# Sheet_MachMQ3.net
KiCad netlist of a schematic drawn in Altium Designer
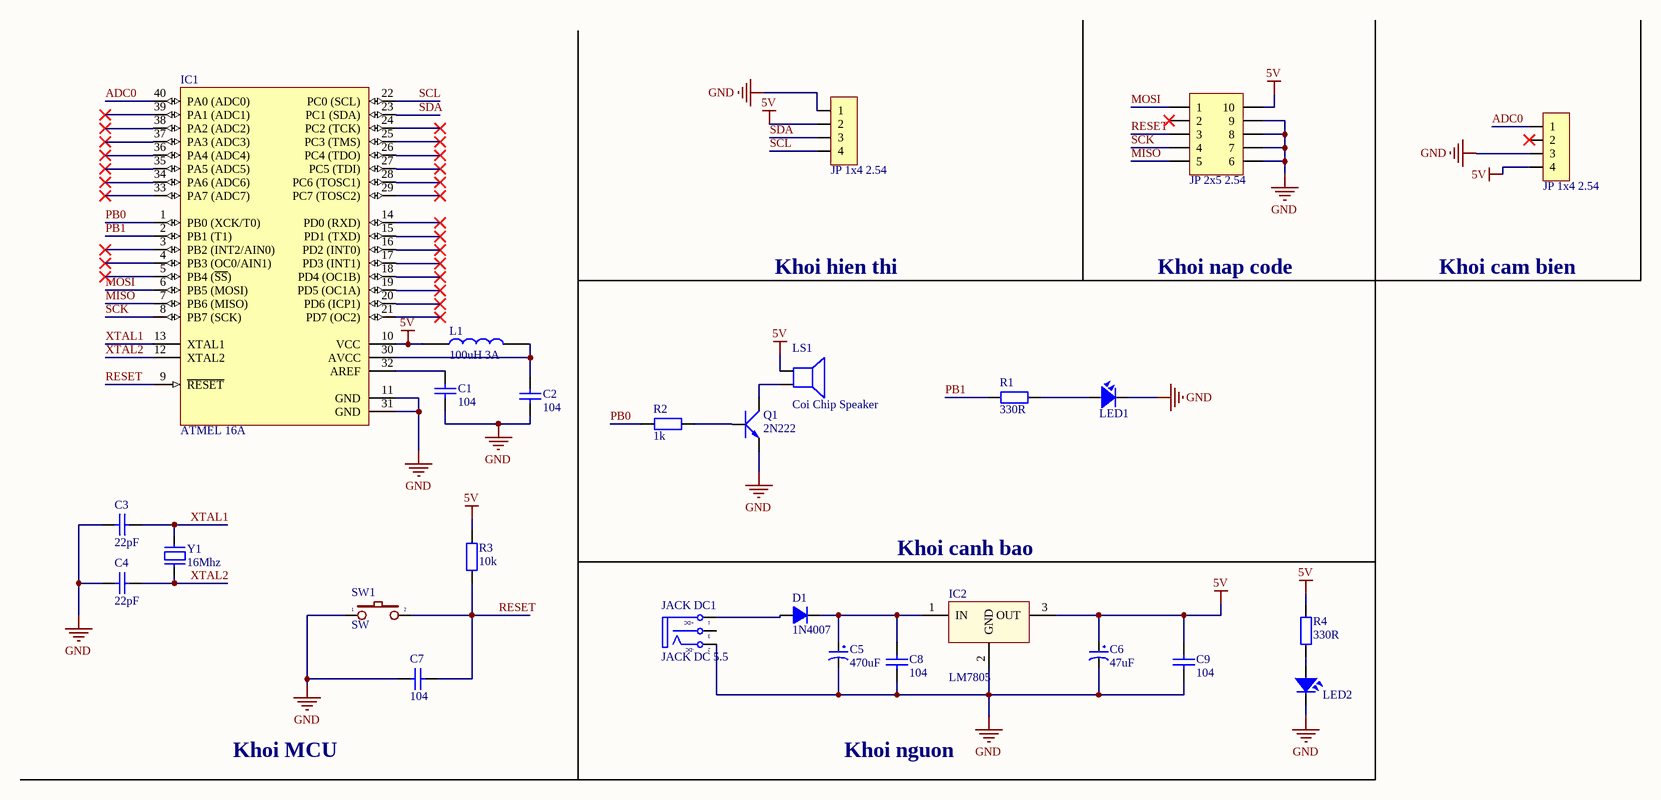
[diagram p0: Sheet_MachMQ3.SchDoc]

(export (version "E")
  (design (tool "Eeschema 10.0.6"))
  (components
    (comp (ref "C1")
      (value "104")
      (footprint "tu gom")
      (description "Cắm")
      (libsource (lib "Capacitor") (part "Tu gom 104 50V"))
    )
    (comp (ref "C2")
      (value "104")
      (footprint "tu gom")
      (description "Cắm")
      (libsource (lib "Capacitor") (part "Tu gom 104 50V"))
    )
    (comp (ref "C3")
      (value "22pF")
      (footprint "tu gom")
      (description "Cắm")
      (libsource (lib "Capacitor") (part "Tu gom 22pF 50V"))
    )
    (comp (ref "C4")
      (value "22pF")
      (footprint "tu gom")
      (description "Cắm")
      (libsource (lib "Capacitor") (part "Tu gom 22pF 50V"))
    )
    (comp (ref "C5")
      (value "470uF")
      (footprint "tu hoa 8mm")
      (description "Cắm")
      (libsource (lib "Capacitor") (part "Tu Hoa 470uF 16V 8x11"))
    )
    (comp (ref "C6")
      (value "47uF")
      (footprint "tu hoa 5mm")
      (description "Cắm")
      (libsource (lib "Capacitor") (part "Tu Hoa 47uF 16V 5x10"))
    )
    (comp (ref "C7")
      (value "104")
      (footprint "tu gom")
      (description "Cắm")
      (libsource (lib "Capacitor") (part "Tu gom 104 50V"))
    )
    (comp (ref "C8")
      (value "104")
      (footprint "tu gom")
      (description "Cắm")
      (libsource (lib "Capacitor") (part "Tu gom 104 50V"))
    )
    (comp (ref "C9")
      (value "104")
      (footprint "tu gom")
      (description "Cắm")
      (libsource (lib "Capacitor") (part "Tu gom 104 50V"))
    )
    (comp (ref "D1")
      (value "1N4007")
      (footprint "D1A")
      (description "Diode 1A")
      (libsource (lib "My Library") (part "D1A"))
    )
    (comp (ref "IC1")
      (value "ATMEL 16A")
      (footprint "DIP40/W0.6")
      (description "8-Bit AVR Microcontroller with 16K Bytes of In-System Programmable Flash Memory")
      (libsource (lib "My Library") (part "ATmega16A-PU"))
    )
    (comp (ref "IC2")
      (value "LM7805")
      (footprint "QTO-220H3")
      (description "On ap +, from + 5 to + 24VDC")
      (libsource (lib "My Library") (part "LM78xx"))
    )
    (comp (ref "JACK DC1")
      (value "JACK DC 5.5")
      (footprint "JACK DC 5.5")
      (libsource (lib "Component") (part "JACK DC 5.5"))
    )
    (comp (ref "JP1")
      (value "JP 1x4 2.54")
      (footprint "JP 1x4 CT")
      (description "Cắm")
      (libsource (lib "Jump") (part "JP 1x4 2.54 Cai Thang"))
    )
    (comp (ref "JP2")
      (value "JP 2x5 2.54")
      (footprint "JP 2x5 DT")
      (description "Cắm")
      (libsource (lib "Jump") (part "JP 2x5 2.54 Duc Thang"))
    )
    (comp (ref "JP3")
      (value "JP 1x4 2.54")
      (footprint "JP 1x4 CT")
      (description "Cắm")
      (libsource (lib "Jump") (part "JP 1x4 2.54 Cai Thang"))
    )
    (comp (ref "L1")
      (value "100uH 3A")
      (footprint "CUON CAM 100uH3A")
      (description "Dán")
      (libsource (lib "Inductor") (part "CUON CAM 100uH DIP"))
    )
    (comp (ref "LED1")
      (value "LED")
      (footprint "LED-3MM-RED")
      (description "LED Single colour Green and Red")
      (libsource (lib "LIBRARY") (part "LED"))
    )
    (comp (ref "LED2")
      (value "LED")
      (footprint "LED-3MM-RED")
      (description "LED Single colour Green and Red")
      (libsource (lib "LIBRARY") (part "LED"))
    )
    (comp (ref "LS1")
      (value "Coi Chip Speaker")
      (footprint "Coi Chip Speacker")
      (description "Còi chip")
      (libsource (lib "Component") (part "Coi Chip Speaker"))
    )
    (comp (ref "Q1")
      (value "2N222")
      (footprint "TO92-123")
      (description "NPN 600mW, ECB")
      (libsource (lib "LIBRARY") (part "2N222"))
    )
    (comp (ref "R1")
      (value "330R")
      (footprint "tro vach 1/2w")
      (description "Cắm")
      (libsource (lib "Resistor") (part "Tro Vach 1/2W 5% 330R"))
    )
    (comp (ref "R2")
      (value "1k")
      (footprint "tro vach 1/2w")
      (description "Cắm")
      (libsource (lib "Resistor") (part "Tro Vach 1/2W 5% 1k"))
    )
    (comp (ref "R3")
      (value "10k")
      (footprint "tro vach 1/2w")
      (description "Cắm")
      (libsource (lib "Resistor") (part "Tro Vach 1/2W 5% 10k"))
    )
    (comp (ref "R4")
      (value "330R")
      (footprint "tro vach 1/2w")
      (description "Cắm")
      (libsource (lib "Resistor") (part "Tro Vach 1/2W 5% 330R"))
    )
    (comp (ref "SW1")
      (value "SW")
      (footprint "SW2")
      (description "Switch button 2 pin")
      (libsource (lib "Library AL") (part "SW2"))
    )
    (comp (ref "Y1")
      (value "16Mhz")
      (footprint "Thach Anh 2 chan cam")
      (description "Crystal For all Crystal 2pin.")
      (libsource (lib "Component") (part "Thach Anh 2 chan Cam"))
    )
  )
  (nets
    (net (code "1") (name "/ADC0") (class "Default")
      (node (ref "IC1") (pin "40") (pinfunction "PA0_(ADC0)_40") (pintype "bidirectional"))
      (node (ref "JP1") (pin "1") (pinfunction "1_1") (pintype "passive"))
    )
    (net (code "2") (name "/MISO") (class "Default")
      (node (ref "IC1") (pin "7") (pinfunction "PB6_(MISO)_7") (pintype "bidirectional"))
      (node (ref "JP2") (pin "5") (pinfunction "5_5") (pintype "passive"))
    )
    (net (code "3") (name "/MOSI") (class "Default")
      (node (ref "IC1") (pin "6") (pinfunction "PB5_(MOSI)_6") (pintype "bidirectional"))
      (node (ref "JP2") (pin "1") (pinfunction "1_1") (pintype "passive"))
    )
    (net (code "4") (name "/PB0") (class "Default")
      (node (ref "IC1") (pin "1") (pinfunction "PB0_(XCK/T0)_1") (pintype "bidirectional"))
      (node (ref "R2") (pin "1") (pinfunction "1_1") (pintype "passive"))
    )
    (net (code "5") (name "/PB1") (class "Default")
      (node (ref "IC1") (pin "2") (pinfunction "PB1_(T1)_2") (pintype "bidirectional"))
      (node (ref "R1") (pin "1") (pinfunction "1_1") (pintype "passive"))
    )
    (net (code "6") (name "/RESET") (class "Default")
      (node (ref "C7") (pin "1") (pinfunction "1_1") (pintype "passive"))
      (node (ref "IC1") (pin "9") (pinfunction "~{RESET}_9") (pintype "input"))
      (node (ref "JP2") (pin "3") (pinfunction "3_3") (pintype "passive"))
      (node (ref "R3") (pin "1") (pinfunction "1_1") (pintype "passive"))
      (node (ref "SW1") (pin "2") (pinfunction "2_2") (pintype "passive"))
    )
    (net (code "7") (name "/SCK") (class "Default")
      (node (ref "IC1") (pin "8") (pinfunction "PB7_(SCK)_8") (pintype "bidirectional"))
      (node (ref "JP2") (pin "4") (pinfunction "4_4") (pintype "passive"))
    )
    (net (code "8") (name "/SCL") (class "Default")
      (node (ref "IC1") (pin "22") (pinfunction "PC0_(SCL)_22") (pintype "bidirectional"))
      (node (ref "JP3") (pin "4") (pinfunction "4_4") (pintype "passive"))
    )
    (net (code "9") (name "/SDA") (class "Default")
      (node (ref "IC1") (pin "23") (pinfunction "PC1_(SDA)_23") (pintype "bidirectional"))
      (node (ref "JP3") (pin "3") (pinfunction "3_3") (pintype "passive"))
    )
    (net (code "10") (name "/XTAL1") (class "Default")
      (node (ref "C3") (pin "1") (pinfunction "1_1") (pintype "passive"))
      (node (ref "IC1") (pin "13") (pinfunction "XTAL1_13") (pintype "passive"))
      (node (ref "Y1") (pin "2") (pinfunction "2_2") (pintype "passive"))
    )
    (net (code "11") (name "/XTAL2") (class "Default")
      (node (ref "C4") (pin "1") (pinfunction "1_1") (pintype "passive"))
      (node (ref "IC1") (pin "12") (pinfunction "XTAL2_12") (pintype "passive"))
      (node (ref "Y1") (pin "1") (pinfunction "1_1") (pintype "passive"))
    )
    (net (code "12") (name "5V") (class "Default")
      (node (ref "C6") (pin "1") (pinfunction "1_1") (pintype "passive"))
      (node (ref "C9") (pin "1") (pinfunction "1_1") (pintype "passive"))
      (node (ref "IC1") (pin "10") (pinfunction "VCC_10") (pintype "power_in"))
      (node (ref "IC2") (pin "3") (pinfunction "OUT_3") (pintype "passive"))
      (node (ref "JP1") (pin "4") (pinfunction "4_4") (pintype "passive"))
      (node (ref "JP2") (pin "10") (pinfunction "10_10") (pintype "passive"))
      (node (ref "JP3") (pin "2") (pinfunction "2_2") (pintype "passive"))
      (node (ref "L1") (pin "1") (pinfunction "1_1") (pintype "passive"))
      (node (ref "LS1") (pin "1") (pinfunction "1_1") (pintype "passive"))
      (node (ref "R3") (pin "2") (pinfunction "2_2") (pintype "passive"))
      (node (ref "R4") (pin "2") (pinfunction "2_2") (pintype "passive"))
    )
    (net (code "13") (name "GND") (class "Default")
      (node (ref "C1") (pin "2") (pinfunction "2_2") (pintype "passive"))
      (node (ref "C2") (pin "2") (pinfunction "2_2") (pintype "passive"))
      (node (ref "C3") (pin "2") (pinfunction "2_2") (pintype "passive"))
      (node (ref "C4") (pin "2") (pinfunction "2_2") (pintype "passive"))
      (node (ref "C5") (pin "2") (pinfunction "2_2") (pintype "passive"))
      (node (ref "C6") (pin "2") (pinfunction "2_2") (pintype "passive"))
      (node (ref "C7") (pin "2") (pinfunction "2_2") (pintype "passive"))
      (node (ref "C8") (pin "2") (pinfunction "2_2") (pintype "passive"))
      (node (ref "C9") (pin "2") (pinfunction "2_2") (pintype "passive"))
      (node (ref "IC1") (pin "11") (pinfunction "GND_11") (pintype "power_in"))
      (node (ref "IC1") (pin "31") (pinfunction "GND_31") (pintype "power_in"))
      (node (ref "IC2") (pin "2") (pinfunction "GND_2") (pintype "passive"))
      (node (ref "JACK DC1") (pin "2") (pinfunction "TN_2") (pintype "passive"))
      (node (ref "JP1") (pin "3") (pinfunction "3_3") (pintype "passive"))
      (node (ref "JP2") (pin "6") (pinfunction "6_6") (pintype "passive"))
      (node (ref "JP2") (pin "7") (pinfunction "7_7") (pintype "passive"))
      (node (ref "JP2") (pin "8") (pinfunction "8_8") (pintype "passive"))
      (node (ref "JP2") (pin "9") (pinfunction "9_9") (pintype "passive"))
      (node (ref "JP3") (pin "1") (pinfunction "1_1") (pintype "passive"))
      (node (ref "LED1") (pin "2") (pinfunction "2_2") (pintype "passive"))
      (node (ref "LED2") (pin "2") (pinfunction "2_2") (pintype "passive"))
      (node (ref "Q1") (pin "1") (pinfunction "E_1") (pintype "passive"))
      (node (ref "SW1") (pin "1") (pinfunction "1_1") (pintype "passive"))
    )
    (net (code "14") (name "Net-(D1-A)") (class "Default")
      (node (ref "D1") (pin "1") (pinfunction "A_1") (pintype "passive"))
      (node (ref "JACK DC1") (pin "1") (pinfunction "T_1") (pintype "passive"))
    )
    (net (code "15") (name "Net-(D1-K)") (class "Default")
      (node (ref "C5") (pin "1") (pinfunction "1_1") (pintype "passive"))
      (node (ref "C8") (pin "1") (pinfunction "1_1") (pintype "passive"))
      (node (ref "D1") (pin "2") (pinfunction "K_2") (pintype "passive"))
      (node (ref "IC2") (pin "1") (pinfunction "IN_1") (pintype "passive"))
    )
    (net (code "16") (name "Net-(IC1-AREF)") (class "Default")
      (node (ref "C1") (pin "1") (pinfunction "1_1") (pintype "passive"))
      (node (ref "IC1") (pin "32") (pinfunction "AREF_32") (pintype "power_in"))
    )
    (net (code "17") (name "Net-(IC1-AVCC)") (class "Default")
      (node (ref "C2") (pin "1") (pinfunction "1_1") (pintype "passive"))
      (node (ref "IC1") (pin "30") (pinfunction "AVCC_30") (pintype "power_in"))
      (node (ref "L1") (pin "2") (pinfunction "2_2") (pintype "passive"))
    )
    (net (code "18") (name "Net-(LED1-Pad1)") (class "Default")
      (node (ref "LED1") (pin "1") (pinfunction "1_1") (pintype "passive"))
      (node (ref "R1") (pin "2") (pinfunction "2_2") (pintype "passive"))
    )
    (net (code "19") (name "Net-(LED2-Pad1)") (class "Default")
      (node (ref "LED2") (pin "1") (pinfunction "1_1") (pintype "passive"))
      (node (ref "R4") (pin "1") (pinfunction "1_1") (pintype "passive"))
    )
    (net (code "20") (name "Net-(Q1-B)") (class "Default")
      (node (ref "Q1") (pin "2") (pinfunction "B_2") (pintype "passive"))
      (node (ref "R2") (pin "2") (pinfunction "2_2") (pintype "passive"))
    )
    (net (code "21") (name "Net-(Q1-C)") (class "Default")
      (node (ref "LS1") (pin "2") (pinfunction "2_2") (pintype "passive"))
      (node (ref "Q1") (pin "3") (pinfunction "C_3") (pintype "passive"))
    )
    (net (code "22") (name "unconnected-(IC1-PA1_(ADC1)-Pad39)") (class "Default")
      (node (ref "IC1") (pin "39") (pinfunction "PA1_(ADC1)_39") (pintype "bidirectional+no_connect"))
    )
    (net (code "23") (name "unconnected-(IC1-PA2_(ADC2)-Pad38)") (class "Default")
      (node (ref "IC1") (pin "38") (pinfunction "PA2_(ADC2)_38") (pintype "bidirectional+no_connect"))
    )
    (net (code "24") (name "unconnected-(IC1-PA3_(ADC3)-Pad37)") (class "Default")
      (node (ref "IC1") (pin "37") (pinfunction "PA3_(ADC3)_37") (pintype "bidirectional+no_connect"))
    )
    (net (code "25") (name "unconnected-(IC1-PA4_(ADC4)-Pad36)") (class "Default")
      (node (ref "IC1") (pin "36") (pinfunction "PA4_(ADC4)_36") (pintype "bidirectional+no_connect"))
    )
    (net (code "26") (name "unconnected-(IC1-PA5_(ADC5)-Pad35)") (class "Default")
      (node (ref "IC1") (pin "35") (pinfunction "PA5_(ADC5)_35") (pintype "bidirectional+no_connect"))
    )
    (net (code "27") (name "unconnected-(IC1-PA6_(ADC6)-Pad34)") (class "Default")
      (node (ref "IC1") (pin "34") (pinfunction "PA6_(ADC6)_34") (pintype "bidirectional+no_connect"))
    )
    (net (code "28") (name "unconnected-(IC1-PA7_(ADC7)-Pad33)") (class "Default")
      (node (ref "IC1") (pin "33") (pinfunction "PA7_(ADC7)_33") (pintype "bidirectional+no_connect"))
    )
    (net (code "29") (name "unconnected-(IC1-PB2_(INT2{slash}AIN0)-Pad3)") (class "Default")
      (node (ref "IC1") (pin "3") (pinfunction "PB2_(INT2/AIN0)_3") (pintype "bidirectional+no_connect"))
    )
    (net (code "30") (name "unconnected-(IC1-PB3_(OC0{slash}AIN1)-Pad4)") (class "Default")
      (node (ref "IC1") (pin "4") (pinfunction "PB3_(OC0/AIN1)_4") (pintype "bidirectional+no_connect"))
    )
    (net (code "31") (name "unconnected-(IC1-PB4_(~{SS})-Pad5)") (class "Default")
      (node (ref "IC1") (pin "5") (pinfunction "PB4_(~{SS})_5") (pintype "bidirectional+no_connect"))
    )
    (net (code "32") (name "unconnected-(IC1-PC2_(TCK)-Pad24)") (class "Default")
      (node (ref "IC1") (pin "24") (pinfunction "PC2_(TCK)_24") (pintype "bidirectional+no_connect"))
    )
    (net (code "33") (name "unconnected-(IC1-PC3_(TMS)-Pad25)") (class "Default")
      (node (ref "IC1") (pin "25") (pinfunction "PC3_(TMS)_25") (pintype "bidirectional+no_connect"))
    )
    (net (code "34") (name "unconnected-(IC1-PC4_(TDO)-Pad26)") (class "Default")
      (node (ref "IC1") (pin "26") (pinfunction "PC4_(TDO)_26") (pintype "bidirectional+no_connect"))
    )
    (net (code "35") (name "unconnected-(IC1-PC5_(TDI)-Pad27)") (class "Default")
      (node (ref "IC1") (pin "27") (pinfunction "PC5_(TDI)_27") (pintype "bidirectional+no_connect"))
    )
    (net (code "36") (name "unconnected-(IC1-PC6_(TOSC1)-Pad28)") (class "Default")
      (node (ref "IC1") (pin "28") (pinfunction "PC6_(TOSC1)_28") (pintype "bidirectional+no_connect"))
    )
    (net (code "37") (name "unconnected-(IC1-PC7_(TOSC2)-Pad29)") (class "Default")
      (node (ref "IC1") (pin "29") (pinfunction "PC7_(TOSC2)_29") (pintype "bidirectional+no_connect"))
    )
    (net (code "38") (name "unconnected-(IC1-PD0_(RXD)-Pad14)") (class "Default")
      (node (ref "IC1") (pin "14") (pinfunction "PD0_(RXD)_14") (pintype "bidirectional+no_connect"))
    )
    (net (code "39") (name "unconnected-(IC1-PD1_(TXD)-Pad15)") (class "Default")
      (node (ref "IC1") (pin "15") (pinfunction "PD1_(TXD)_15") (pintype "bidirectional+no_connect"))
    )
    (net (code "40") (name "unconnected-(IC1-PD2_(INT0)-Pad16)") (class "Default")
      (node (ref "IC1") (pin "16") (pinfunction "PD2_(INT0)_16") (pintype "bidirectional+no_connect"))
    )
    (net (code "41") (name "unconnected-(IC1-PD3_(INT1)-Pad17)") (class "Default")
      (node (ref "IC1") (pin "17") (pinfunction "PD3_(INT1)_17") (pintype "bidirectional+no_connect"))
    )
    (net (code "42") (name "unconnected-(IC1-PD4_(OC1B)-Pad18)") (class "Default")
      (node (ref "IC1") (pin "18") (pinfunction "PD4_(OC1B)_18") (pintype "bidirectional+no_connect"))
    )
    (net (code "43") (name "unconnected-(IC1-PD5_(OC1A)-Pad19)") (class "Default")
      (node (ref "IC1") (pin "19") (pinfunction "PD5_(OC1A)_19") (pintype "bidirectional+no_connect"))
    )
    (net (code "44") (name "unconnected-(IC1-PD6_(ICP1)-Pad20)") (class "Default")
      (node (ref "IC1") (pin "20") (pinfunction "PD6_(ICP1)_20") (pintype "bidirectional+no_connect"))
    )
    (net (code "45") (name "unconnected-(IC1-PD7_(OC2)-Pad21)") (class "Default")
      (node (ref "IC1") (pin "21") (pinfunction "PD7_(OC2)_21") (pintype "bidirectional+no_connect"))
    )
    (net (code "46") (name "unconnected-(JACK DC1-S-Pad3)") (class "Default")
      (node (ref "JACK DC1") (pin "3") (pinfunction "S_3") (pintype "power_in"))
    )
    (net (code "47") (name "unconnected-(JP1-Pad2)") (class "Default")
      (node (ref "JP1") (pin "2") (pinfunction "2_2") (pintype "passive+no_connect"))
    )
    (net (code "48") (name "unconnected-(JP2-Pad2)") (class "Default")
      (node (ref "JP2") (pin "2") (pinfunction "2_2") (pintype "passive+no_connect"))
    )
  )
)
